# LCD.net
KiCad netlist of a schematic drawn in Altium Designer
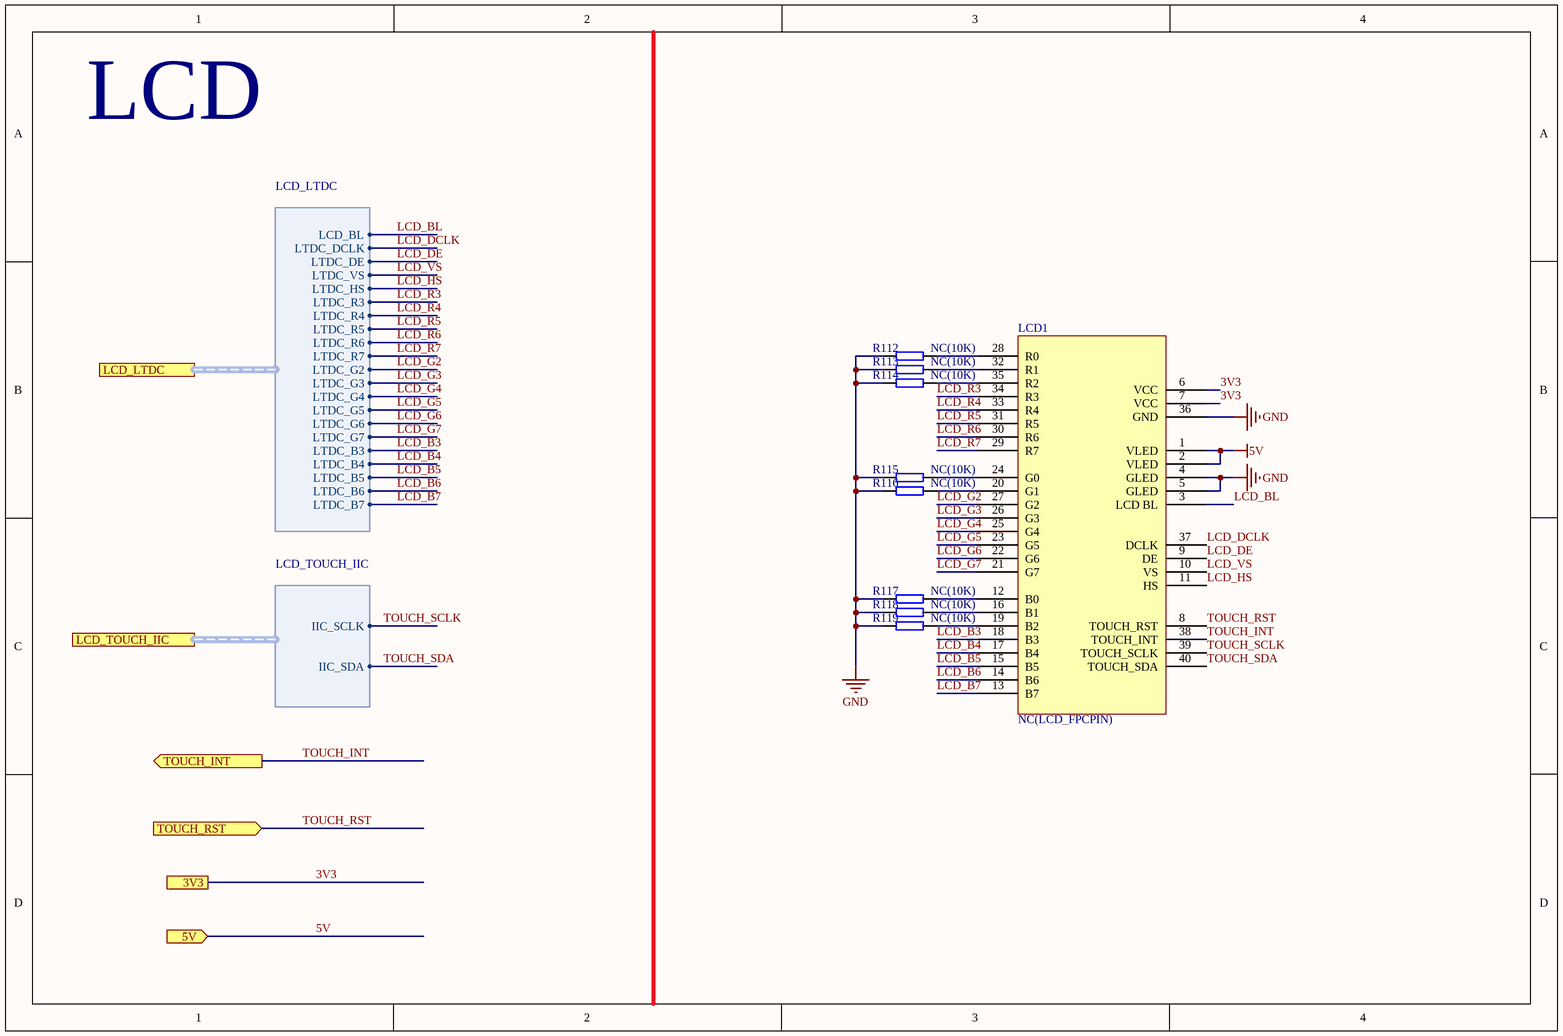
[diagram p0: LCD.SchDoc]

(export (version "E")
  (design (tool "Eeschema 10.0.6"))
  (components
    (comp (ref "LCD1")
      (value "NC(LCD_FPCPIN)")
      (footprint "FPC40P-0.5-FK750M3")
      (libsource (lib "MY-显示") (part "MY-RGB"))
    )
    (comp (ref "R112") (value "NC(10K)") (footprint "0402") (libsource (lib "*") (part "RES")))
    (comp (ref "R113") (value "NC(10K)") (footprint "0402") (libsource (lib "*") (part "RES")))
    (comp (ref "R114") (value "NC(10K)") (footprint "0402") (libsource (lib "*") (part "RES")))
    (comp (ref "R115") (value "NC(10K)") (footprint "0402") (libsource (lib "*") (part "RES")))
    (comp (ref "R116") (value "NC(10K)") (footprint "0402") (libsource (lib "*") (part "RES")))
    (comp (ref "R117") (value "NC(10K)") (footprint "0402") (libsource (lib "*") (part "RES")))
    (comp (ref "R118") (value "NC(10K)") (footprint "0402") (libsource (lib "*") (part "RES")))
    (comp (ref "R119") (value "NC(10K)") (footprint "0402") (libsource (lib "*") (part "RES")))
  )
  (nets
    (net (code "3") (name "/3V3") (class "Default")
      (node (ref "LCD1") (pin "6") (pinfunction "VCC_6") (pintype "passive"))
      (node (ref "LCD1") (pin "7") (pinfunction "VCC_7") (pintype "passive"))
    )
    (net (code "4") (name "/LCD_B3") (class "Default")
      (node (ref "LCD1") (pin "18") (pinfunction "B3_18") (pintype "passive"))
    )
    (net (code "5") (name "/LCD_B4") (class "Default")
      (node (ref "LCD1") (pin "17") (pinfunction "B4_17") (pintype "passive"))
    )
    (net (code "6") (name "/LCD_B5") (class "Default")
      (node (ref "LCD1") (pin "15") (pinfunction "B5_15") (pintype "passive"))
    )
    (net (code "7") (name "/LCD_B6") (class "Default")
      (node (ref "LCD1") (pin "14") (pinfunction "B6_14") (pintype "passive"))
    )
    (net (code "8") (name "/LCD_B7") (class "Default")
      (node (ref "LCD1") (pin "13") (pinfunction "B7_13") (pintype "passive"))
    )
    (net (code "9") (name "/LCD_BL") (class "Default")
      (node (ref "LCD1") (pin "3") (pinfunction "LCD_BL_3") (pintype "passive"))
    )
    (net (code "10") (name "/LCD_DCLK") (class "Default")
      (node (ref "LCD1") (pin "37") (pinfunction "DCLK_37") (pintype "passive"))
    )
    (net (code "11") (name "/LCD_DE") (class "Default")
      (node (ref "LCD1") (pin "9") (pinfunction "DE_9") (pintype "passive"))
    )
    (net (code "12") (name "/LCD_G2") (class "Default")
      (node (ref "LCD1") (pin "27") (pinfunction "G2_27") (pintype "passive"))
    )
    (net (code "13") (name "/LCD_G3") (class "Default")
      (node (ref "LCD1") (pin "26") (pinfunction "G3_26") (pintype "passive"))
    )
    (net (code "14") (name "/LCD_G4") (class "Default")
      (node (ref "LCD1") (pin "25") (pinfunction "G4_25") (pintype "passive"))
    )
    (net (code "15") (name "/LCD_G5") (class "Default")
      (node (ref "LCD1") (pin "23") (pinfunction "G5_23") (pintype "passive"))
    )
    (net (code "16") (name "/LCD_G6") (class "Default")
      (node (ref "LCD1") (pin "22") (pinfunction "G6_22") (pintype "passive"))
    )
    (net (code "17") (name "/LCD_G7") (class "Default")
      (node (ref "LCD1") (pin "21") (pinfunction "G7_21") (pintype "passive"))
    )
    (net (code "18") (name "/LCD_HS") (class "Default")
      (node (ref "LCD1") (pin "11") (pinfunction "HS_11") (pintype "passive"))
    )
    (net (code "19") (name "/LCD_R3") (class "Default")
      (node (ref "LCD1") (pin "34") (pinfunction "R3_34") (pintype "passive"))
    )
    (net (code "20") (name "/LCD_R4") (class "Default")
      (node (ref "LCD1") (pin "33") (pinfunction "R4_33") (pintype "passive"))
    )
    (net (code "21") (name "/LCD_R5") (class "Default")
      (node (ref "LCD1") (pin "31") (pinfunction "R5_31") (pintype "passive"))
    )
    (net (code "22") (name "/LCD_R6") (class "Default")
      (node (ref "LCD1") (pin "30") (pinfunction "R6_30") (pintype "passive"))
    )
    (net (code "23") (name "/LCD_R7") (class "Default")
      (node (ref "LCD1") (pin "29") (pinfunction "R7_29") (pintype "passive"))
    )
    (net (code "24") (name "/LCD_VS") (class "Default")
      (node (ref "LCD1") (pin "10") (pinfunction "VS_10") (pintype "passive"))
    )
    (net (code "25") (name "/TOUCH_INT") (class "Default")
      (node (ref "LCD1") (pin "38") (pinfunction "TOUCH_INT_38") (pintype "passive"))
    )
    (net (code "26") (name "/TOUCH_RST") (class "Default")
      (node (ref "LCD1") (pin "8") (pinfunction "TOUCH_RST_8") (pintype "passive"))
    )
    (net (code "27") (name "/TOUCH_SCLK") (class "Default")
      (node (ref "LCD1") (pin "39") (pinfunction "TOUCH_SCLK_39") (pintype "passive"))
    )
    (net (code "28") (name "/TOUCH_SDA") (class "Default")
      (node (ref "LCD1") (pin "40") (pinfunction "TOUCH_SDA_40") (pintype "passive"))
    )
    (net (code "31") (name "5V") (class "Default")
      (node (ref "LCD1") (pin "1") (pinfunction "VLED_1") (pintype "passive"))
      (node (ref "LCD1") (pin "2") (pinfunction "VLED_2") (pintype "passive"))
    )
    (net (code "32") (name "GND") (class "Default")
      (node (ref "LCD1") (pin "36") (pinfunction "GND_36") (pintype "passive"))
      (node (ref "LCD1") (pin "4") (pinfunction "GLED_4") (pintype "passive"))
      (node (ref "LCD1") (pin "5") (pinfunction "GLED_5") (pintype "passive"))
      (node (ref "R112") (pin "2") (pintype "passive"))
      (node (ref "R113") (pin "2") (pintype "passive"))
      (node (ref "R114") (pin "2") (pintype "passive"))
      (node (ref "R115") (pin "2") (pintype "passive"))
      (node (ref "R116") (pin "2") (pintype "passive"))
      (node (ref "R117") (pin "2") (pintype "passive"))
      (node (ref "R118") (pin "2") (pintype "passive"))
      (node (ref "R119") (pin "2") (pintype "passive"))
    )
    (net (code "33") (name "Net-(LCD1-B0)") (class "Default")
      (node (ref "LCD1") (pin "12") (pinfunction "B0_12") (pintype "passive"))
      (node (ref "R117") (pin "1") (pintype "passive"))
    )
    (net (code "34") (name "Net-(LCD1-B1)") (class "Default")
      (node (ref "LCD1") (pin "16") (pinfunction "B1_16") (pintype "passive"))
      (node (ref "R118") (pin "1") (pintype "passive"))
    )
    (net (code "35") (name "Net-(LCD1-B2)") (class "Default")
      (node (ref "LCD1") (pin "19") (pinfunction "B2_19") (pintype "passive"))
      (node (ref "R119") (pin "1") (pintype "passive"))
    )
    (net (code "36") (name "Net-(LCD1-G0)") (class "Default")
      (node (ref "LCD1") (pin "24") (pinfunction "G0_24") (pintype "passive"))
      (node (ref "R115") (pin "1") (pintype "passive"))
    )
    (net (code "37") (name "Net-(LCD1-G1)") (class "Default")
      (node (ref "LCD1") (pin "20") (pinfunction "G1_20") (pintype "passive"))
      (node (ref "R116") (pin "1") (pintype "passive"))
    )
    (net (code "38") (name "Net-(LCD1-R0)") (class "Default")
      (node (ref "LCD1") (pin "28") (pinfunction "R0_28") (pintype "passive"))
      (node (ref "R112") (pin "1") (pintype "passive"))
    )
    (net (code "39") (name "Net-(LCD1-R1)") (class "Default")
      (node (ref "LCD1") (pin "32") (pinfunction "R1_32") (pintype "passive"))
      (node (ref "R113") (pin "1") (pintype "passive"))
    )
    (net (code "40") (name "Net-(LCD1-R2)") (class "Default")
      (node (ref "LCD1") (pin "35") (pinfunction "R2_35") (pintype "passive"))
      (node (ref "R114") (pin "1") (pintype "passive"))
    )
  )
)
